# Power_Delivery.net
KiCad netlist of a schematic drawn in Altium Designer
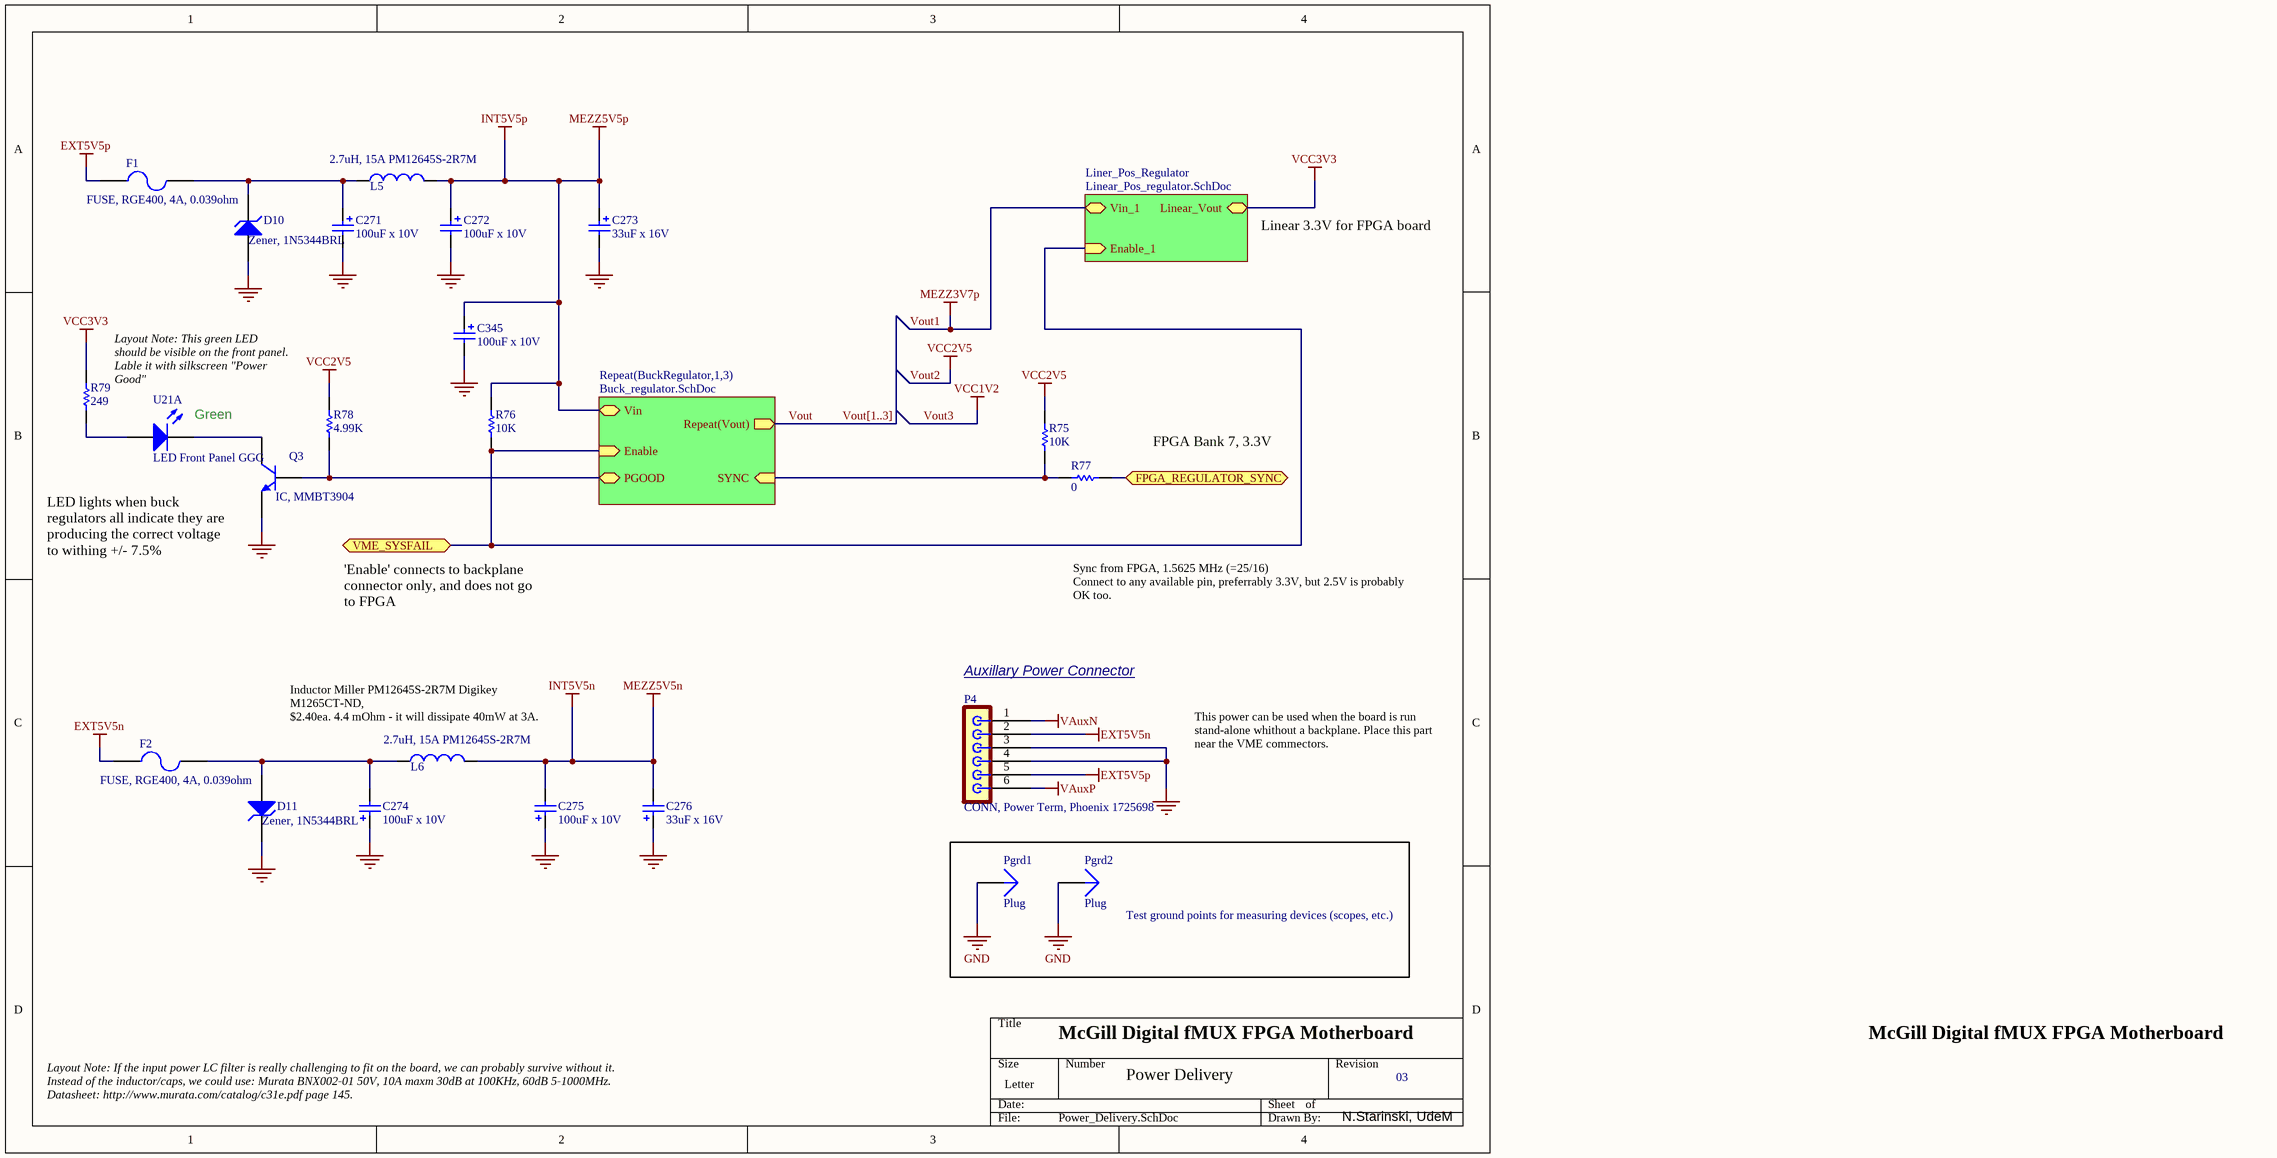
[diagram p0: Power_Delivery.SchDoc]

(export (version "E")
  (design (tool "Eeschema 10.0.6"))
  (components
    (comp (ref "C271")
      (value "100uF x 10V")
      (footprint "TC6032-2412")
      (description "CAP TANTC TPSC107K010R0075")
      (fields (field (name "PUBLISHER") "Altium Limited"))
      (libsource (lib "Miscellaneous Devices 02") (part "Cap Pol3"))
    )
    (comp (ref "C272")
      (value "100uF x 10V")
      (footprint "TC6032-2412")
      (description "CAP TANTC TPSC107K010R0075")
      (fields (field (name "PUBLISHER") "Altium Limited"))
      (libsource (lib "Miscellaneous Devices 02") (part "Cap Pol3"))
    )
    (comp (ref "C273")
      (value "33uF x 16V")
      (footprint "CC4532-1812")
      (description "CAP POL C4532X5R1C336M")
      (fields (field (name "PUBLISHER") "Altium Limited"))
      (libsource (lib "Miscellaneous Devices") (part "Cap Pol3"))
    )
    (comp (ref "C274")
      (value "100uF x 10V")
      (footprint "TC6032-2412")
      (description "CAP TANTC TPSC107K010R0075")
      (fields (field (name "PUBLISHER") "Altium Limited"))
      (libsource (lib "Miscellaneous Devices 02") (part "Cap Pol3"))
    )
    (comp (ref "C275")
      (value "100uF x 10V")
      (footprint "TC6032-2412")
      (description "CAP TANTC TPSC107K010R0075")
      (fields (field (name "PUBLISHER") "Altium Limited"))
      (libsource (lib "Miscellaneous Devices 02") (part "Cap Pol3"))
    )
    (comp (ref "C276")
      (value "33uF x 16V")
      (footprint "CC4532-1812")
      (description "CAP POL C4532X5R1C336M")
      (fields (field (name "PUBLISHER") "Altium Limited"))
      (libsource (lib "Miscellaneous Devices") (part "Cap Pol3"))
    )
    (comp (ref "C345")
      (value "100uF x 10V")
      (footprint "TC6032-2412")
      (description "CAP TANTC TPSC107K010R0075")
      (fields (field (name "PUBLISHER") "Altium Limited"))
      (libsource (lib "Miscellaneous Devices 02") (part "Cap Pol3"))
    )
    (comp (ref "D10")
      (value "Zener, 1N5344BRL")
      (footprint "DIODE-0.7")
      (description "Zener Diode, 8.2V, 5W")
      (fields (field (name "PUBLISHER") "Altium Limited"))
      (libsource (lib "Miscellaneous Devices") (part "D Zener"))
    )
    (comp (ref "D11")
      (value "Zener, 1N5344BRL")
      (footprint "DIODE-0.7")
      (description "Zener Diode, 8.2V, 5W")
      (fields (field (name "PUBLISHER") "Altium Limited"))
      (libsource (lib "Miscellaneous Devices") (part "D Zener"))
    )
    (comp (ref "F1")
      (value "FUSE, RGE400, 4A, 0.039ohm")
      (footprint "Fuse 5.88mm")
      (description "Fuse")
      (fields (field (name "PUBLISHER") "Altium Limited"))
      (libsource (lib "Miscellaneous Devices 02") (part "Fuse 2"))
    )
    (comp (ref "F2")
      (value "FUSE, RGE400, 4A, 0.039ohm")
      (footprint "Fuse 5.88mm")
      (description "Fuse")
      (fields (field (name "PUBLISHER") "Altium Limited"))
      (libsource (lib "Miscellaneous Devices 02") (part "Fuse 2"))
    )
    (comp (ref "L5")
      (value "2.7uH, 15A PM12645S-2R7M")
      (footprint "MLC_inductor")
      (description "Inductor")
      (fields (field (name "PUBLISHER") "Altium Limited"))
      (libsource (lib "Miscellaneous Devices") (part "Inductor"))
    )
    (comp (ref "L6")
      (value "2.7uH, 15A PM12645S-2R7M")
      (footprint "MLC_inductor")
      (description "Inductor")
      (fields (field (name "PUBLISHER") "Altium Limited"))
      (libsource (lib "Miscellaneous Devices") (part "Inductor"))
    )
    (comp (ref "P4")
      (value "CONN, Power Term, Phoenix 1725698")
      (footprint "TrmBlk6")
      (description "MPT 0.5/6-2.54 Terminal Block")
      (libsource (lib "Miscellaneous Devices 02") (part "TrmBlk_6pos"))
    )
    (comp (ref "Pgrd1")
      (value "Plug")
      (footprint "PIN1")
      (fields (field (name "PUBLISHER") "Altium Limited"))
      (libsource (lib "Miscellaneous Connectors") (part "Plug"))
    )
    (comp (ref "Pgrd2")
      (value "Plug")
      (footprint "PIN1")
      (fields (field (name "PUBLISHER") "Altium Limited"))
      (libsource (lib "Miscellaneous Connectors") (part "Plug"))
    )
    (comp (ref "Q3")
      (value "IC, MMBT3904")
      (footprint "SOT23")
      (description "NPN Switching Transistor")
      (fields (field (name "PUBLISHER") "Altium Limited"))
      (libsource (lib "Philips Discrete BJT - Low Power") (part "MMBT3904"))
    )
    (comp (ref "R75")
      (value "10K")
      (footprint "CR1608-0603")
      (description "Resistor 0603")
      (fields (field (name "PUBLISHER") "Altium Limited"))
      (libsource (lib "Miscellaneous Devices") (part "Res Semi"))
    )
    (comp (ref "R76")
      (value "10K")
      (footprint "CR1608-0603")
      (description "Resistor 0603")
      (fields (field (name "PUBLISHER") "Altium Limited"))
      (libsource (lib "Miscellaneous Devices") (part "Res Semi"))
    )
    (comp (ref "R77")
      (value "0")
      (footprint "CR1608-0603")
      (description "Resistor 0603")
      (fields (field (name "PUBLISHER") "Altium Limited"))
      (libsource (lib "Miscellaneous Devices") (part "Res Semi"))
    )
    (comp (ref "R78")
      (value "4.99K")
      (footprint "CR1608-0603")
      (description "Resistor 0603")
      (fields (field (name "PUBLISHER") "Altium Limited"))
      (libsource (lib "Miscellaneous Devices") (part "Res Semi"))
    )
    (comp (ref "R79")
      (value "249")
      (footprint "CR1608-0603")
      (description "Resistor 0603")
      (fields (field (name "PUBLISHER") "Altium Limited"))
      (libsource (lib "Miscellaneous Devices") (part "Res Semi"))
    )
    (comp (ref "U21")
      (value "LED Front Panel GGG")
      (footprint "LED_Tri_")
      (description "564-0200-222F")
      (libsource (lib "Miscellaneous Devices") (part "LED_Tri"))
    )
  )
  (nets
    (net (code "1") (name "/FPGA_REGULATOR_SYNC") (class "Default")
      (node (ref "R77") (pin "2") (pinfunction "2_2") (pintype "passive"))
    )
    (net (code "2") (name "/PGOOD") (class "Default")
      (node (ref "Q3") (pin "1") (pinfunction "B_1") (pintype "passive"))
      (node (ref "R78") (pin "1") (pinfunction "1_1") (pintype "passive"))
    )
    (net (code "3") (name "/SYNC") (class "Default")
      (node (ref "R75") (pin "1") (pinfunction "1_1") (pintype "passive"))
      (node (ref "R77") (pin "1") (pinfunction "1_1") (pintype "passive"))
    )
    (net (code "4") (name "/VME_SYSFAIL") (class "Default")
      (node (ref "R76") (pin "1") (pinfunction "1_1") (pintype "passive"))
    )
    (net (code "7") (name "EXT5V5n") (class "Default")
      (node (ref "F2") (pin "1") (pinfunction "1_1") (pintype "passive"))
      (node (ref "P4") (pin "2") (pinfunction "2_2") (pintype "passive"))
    )
    (net (code "8") (name "EXT5V5p") (class "Default")
      (node (ref "F1") (pin "1") (pinfunction "1_1") (pintype "passive"))
      (node (ref "P4") (pin "5") (pinfunction "5_5") (pintype "passive"))
    )
    (net (code "9") (name "GND") (class "Default")
      (node (ref "C271") (pin "2") (pinfunction "2_2") (pintype "passive"))
      (node (ref "C272") (pin "2") (pinfunction "2_2") (pintype "passive"))
      (node (ref "C273") (pin "2") (pinfunction "2_2") (pintype "passive"))
      (node (ref "C274") (pin "1") (pinfunction "1_1") (pintype "passive"))
      (node (ref "C275") (pin "1") (pinfunction "1_1") (pintype "passive"))
      (node (ref "C276") (pin "1") (pinfunction "1_1") (pintype "passive"))
      (node (ref "C345") (pin "2") (pinfunction "2_2") (pintype "passive"))
      (node (ref "D10") (pin "1") (pinfunction "A_1") (pintype "passive"))
      (node (ref "D11") (pin "2") (pinfunction "K_2") (pintype "passive"))
      (node (ref "P4") (pin "3") (pinfunction "3_3") (pintype "passive"))
      (node (ref "P4") (pin "4") (pinfunction "4_4") (pintype "passive"))
      (node (ref "Pgrd1") (pin "1") (pinfunction "1_1") (pintype "passive"))
      (node (ref "Pgrd2") (pin "1") (pinfunction "1_1") (pintype "passive"))
      (node (ref "Q3") (pin "2") (pinfunction "E_2") (pintype "passive"))
    )
    (net (code "10") (name "INT5V5n") (class "Default")
      (node (ref "C275") (pin "2") (pinfunction "2_2") (pintype "passive"))
      (node (ref "C276") (pin "2") (pinfunction "2_2") (pintype "passive"))
      (node (ref "L6") (pin "2") (pinfunction "2_2") (pintype "passive"))
    )
    (net (code "11") (name "INT5V5p") (class "Default")
      (node (ref "C272") (pin "1") (pinfunction "1_1") (pintype "passive"))
      (node (ref "C273") (pin "1") (pinfunction "1_1") (pintype "passive"))
      (node (ref "C345") (pin "1") (pinfunction "1_1") (pintype "passive"))
      (node (ref "L5") (pin "2") (pinfunction "2_2") (pintype "passive"))
      (node (ref "R76") (pin "2") (pinfunction "2_2") (pintype "passive"))
    )
    (net (code "13") (name "Net-(D10-K)") (class "Default")
      (node (ref "C271") (pin "1") (pinfunction "1_1") (pintype "passive"))
      (node (ref "D10") (pin "2") (pinfunction "K_2") (pintype "passive"))
      (node (ref "F1") (pin "2") (pinfunction "2_2") (pintype "passive"))
      (node (ref "L5") (pin "1") (pinfunction "1_1") (pintype "passive"))
    )
    (net (code "14") (name "Net-(D11-A)") (class "Default")
      (node (ref "C274") (pin "2") (pinfunction "2_2") (pintype "passive"))
      (node (ref "D11") (pin "1") (pinfunction "A_1") (pintype "passive"))
      (node (ref "F2") (pin "2") (pinfunction "2_2") (pintype "passive"))
      (node (ref "L6") (pin "1") (pinfunction "1_1") (pintype "passive"))
    )
    (net (code "15") (name "Net-(Q3-C)") (class "Default")
      (node (ref "Q3") (pin "3") (pinfunction "C_3") (pintype "passive"))
      (node (ref "U21") (pin "K1") (pinfunction "K_K1") (pintype "passive"))
    )
    (net (code "16") (name "Net-(U21A-A)") (class "Default")
      (node (ref "R79") (pin "1") (pinfunction "1_1") (pintype "passive"))
      (node (ref "U21") (pin "A1") (pinfunction "A_A1") (pintype "passive"))
    )
    (net (code "17") (name "VAuxN") (class "Default")
      (node (ref "P4") (pin "1") (pinfunction "1_1") (pintype "passive"))
    )
    (net (code "18") (name "VAuxP") (class "Default")
      (node (ref "P4") (pin "6") (pinfunction "6_6") (pintype "passive"))
    )
    (net (code "20") (name "VCC2V5") (class "Default")
      (node (ref "R75") (pin "2") (pinfunction "2_2") (pintype "passive"))
      (node (ref "R78") (pin "2") (pinfunction "2_2") (pintype "passive"))
    )
    (net (code "21") (name "VCC3V3") (class "Default")
      (node (ref "R79") (pin "2") (pinfunction "2_2") (pintype "passive"))
    )
  )
)
